# 12V_Horn_Schematic.net
KiCad netlist of a schematic drawn in Altium Designer
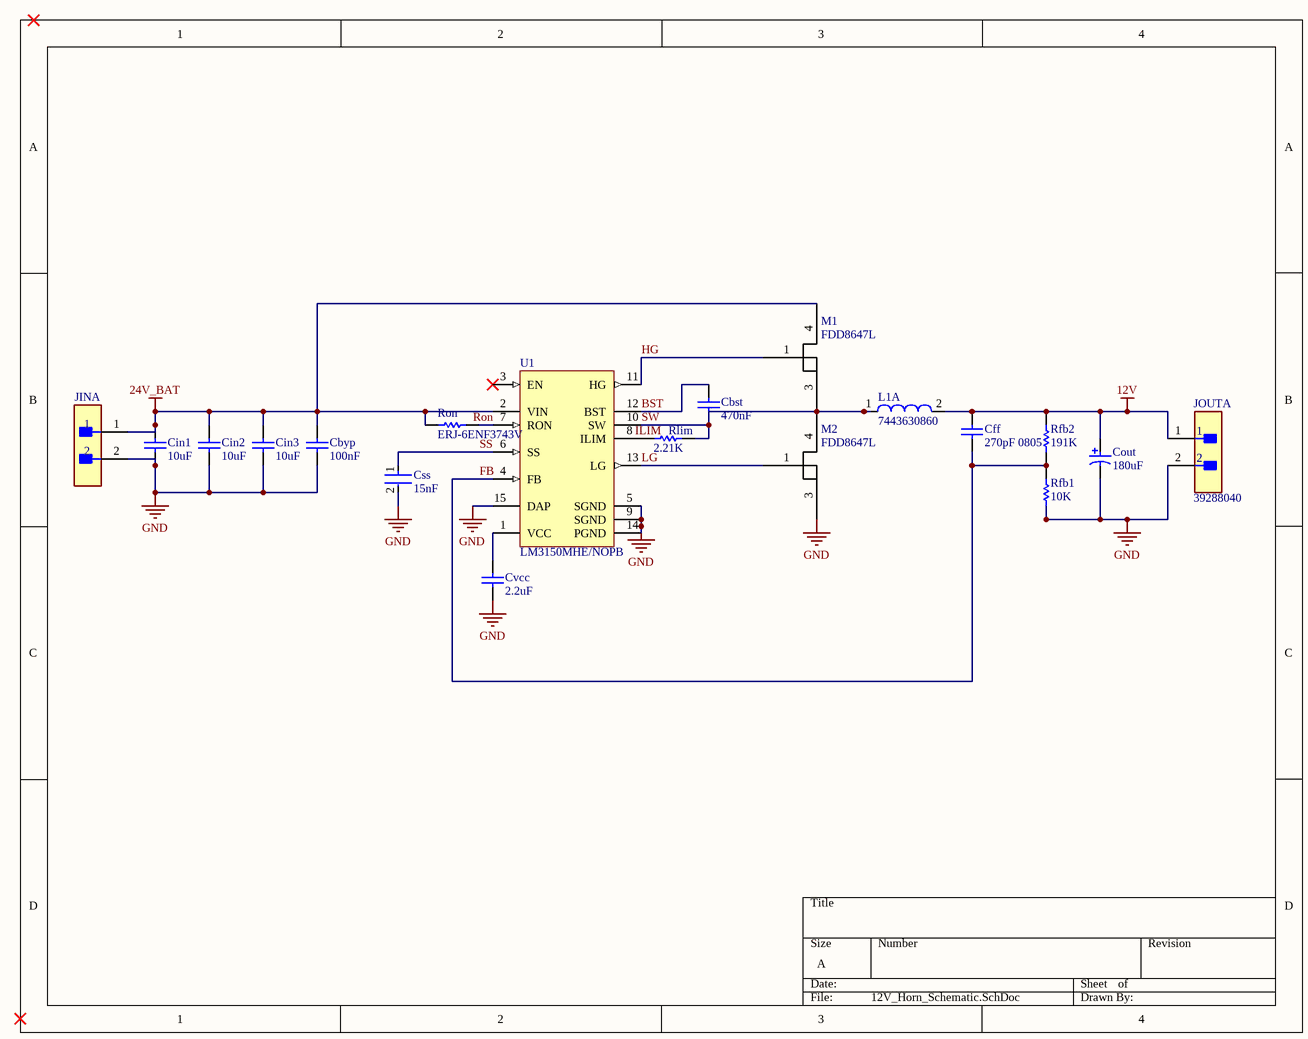
[diagram p0: 12V_Horn_Schematic.SchDoc]

(export (version "E")
  (design (tool "Eeschema 10.0.6"))
  (components
    (comp (ref "Cbst")
      (value "470nF")
      (footprint "CAPC1608X90X35ML10T15")
      (fields (field (name "PART NUMBER") "GRM188R60J474KA01D") (field (name "MANUFACTURER") "Murata"))
      (libsource (lib "Altium Content Vault") (part "CAP"))
    )
    (comp (ref "Cbyp")
      (value "100nF")
      (footprint "CAPC0805(2012)100_M")
      (description "CAP 100nF 50V ±20% 0805 (2012 Metric) Thickness 1mm SMD")
      (fields (field (name "TOLERANCE") "Â±20%"))
      (libsource (lib "Altium Content Vault") (part "CAP"))
    )
    (comp (ref "Cff")
      (value "270pF 0805")
      (footprint "CAPC0805(2012)75_M")
      (description "CAP 270pF 100V ±5% 0805 (2012 Metric) Thickness 0.75mm SMD")
      (fields (field (name "TOLERANCE") "Â±5%"))
      (libsource (lib "Altium Content Vault") (part "CAP"))
    )
    (comp (ref "Cin1")
      (value "10uF")
      (footprint "CAPC3225X270X30LL30")
      (description "Chip Capacitor, 10 uF, +/- 10%, 63 V, -55 to 125 degC, 1210 (3225 Metric), RoHS, Tape and Reel")
      (fields (field (name "VOLTAGE") "63V") (field (name "TOLERANCE") "10%"))
      (libsource (lib "Altium Content Vault") (part "CAP-NP-2"))
    )
    (comp (ref "Cin2")
      (value "10uF")
      (footprint "CAPC3225X270X30LL30")
      (description "Chip Capacitor, 10 uF, +/- 10%, 63 V, -55 to 125 degC, 1210 (3225 Metric), RoHS, Tape and Reel")
      (fields (field (name "VOLTAGE") "63V") (field (name "TOLERANCE") "10%"))
      (libsource (lib "Altium Content Vault") (part "CAP-NP-2"))
    )
    (comp (ref "Cin3")
      (value "10uF")
      (footprint "CAPC3225X270X30LL30")
      (description "Chip Capacitor, 10 uF, +/- 10%, 63 V, -55 to 125 degC, 1210 (3225 Metric), RoHS, Tape and Reel")
      (fields (field (name "VOLTAGE") "63V") (field (name "TOLERANCE") "10%"))
      (libsource (lib "Altium Content Vault") (part "CAP-NP-2"))
    )
    (comp (ref "Cout")
      (value "180uF")
      (footprint "PNSC-SVP-F8_L")
      (fields (field (name "VOLTAGE") "16VDC") (field (name "MANUFACTURER") "Panasonic"))
      (libsource (lib "Altium Content Vault") (part "CAP-P-2"))
    )
    (comp (ref "Css")
      (value "15nF")
      (footprint "FP-CGA4J-IPC_B")
      (description "Cap Ceramic 15nF 50V C0G 5% Pad SMD 0805 +125°C Automotive T/R")
      (fields (field (name "TOLERANCE") "5%"))
      (libsource (lib "Altium Content Vault") (part "b4654b650e69147ec39a6b967a45e02"))
    )
    (comp (ref "Cvcc")
      (value "2.2uF")
      (footprint "CAPC2013X135X50ML10T20")
      (fields (field (name "PART NUMBER") "GRM21BR71A225KA01L") (field (name "MANUFACTURER") "Murata"))
      (libsource (lib "Altium Content Vault") (part "CAP"))
    )
    (comp (ref "JIN")
      (value "39288040")
      (footprint "FP-39288040-MFG")
      (description "CONN HEADER VERT 4POS 4.2MM")
      (fields
        (field (name "MANUFACTURER") "Molex")
        (field (name "OCTOPART") "https://octopart.com/39-28-8040-molex-25241")
      )
      (libsource (lib "") (part "29c4d052ea7803862a8eb5e05759d1e_1"))
    )
    (comp (ref "JOUT")
      (value "39288040")
      (footprint "FP-39288040-MFG")
      (description "CONN HEADER VERT 4POS 4.2MM")
      (fields
        (field (name "MANUFACTURER") "Molex")
        (field (name "OCTOPART") "https://octopart.com/39-28-8040-molex-25241")
      )
      (libsource (lib "Altium Content Vault") (part "29c4d052ea7803862a8eb5e05759d1e"))
    )
    (comp (ref "L1")
      (value "7443630860")
      (footprint "WE-HCF-2013")
      (description "SMD High Current Inductor WE-HCF, L=8.60 µH")
      (libsource (lib "Altium Content Vault") (part "PAS-IND-INDUCTOR-3"))
    )
    (comp (ref "M1") (value "FDD8647L") (footprint "FDD86471L") (libsource (lib "Schlib1") (part "FDD8647L")))
    (comp (ref "M2") (value "FDD8647L") (footprint "FDD86471L") (libsource (lib "Schlib1") (part "FDD8647L")))
    (comp (ref "Rfb1")
      (value "10K")
      (footprint "RESC2013X50X30NL20T20")
      (fields (field (name "MANUFACTURER") "Vishay Dale") (field (name "PART NUMBER") "CRCW080510K0FKEA"))
      (libsource (lib "Altium Content Vault") (part "RES"))
    )
    (comp (ref "Rfb2")
      (value "191K")
      (footprint "RESC2013X70X40ML20T20")
      (fields (field (name "MANUFACTURER") "Panasonic") (field (name "PART NUMBER") "ERJ-6ENF1913V"))
      (libsource (lib "Altium Content Vault") (part "RES"))
    )
    (comp (ref "Rlim")
      (value "2.21K")
      (footprint "RESC2013X50X30NL20T20")
      (fields (field (name "MANUFACTURER") "Vishay Dale") (field (name "PART NUMBER") "CRCW08052K21FKEA"))
      (libsource (lib "Altium Content Vault") (part "RES"))
    )
    (comp (ref "Ron")
      (value "ERJ-6ENF3743V")
      (footprint "RESC2013X70X40LL20T20")
      (fields (field (name "MANUFACTURER") "Panasonic"))
      (libsource (lib "Altium Content Vault") (part "RES"))
    )
    (comp (ref "U1")
      (value "LM3150MHE/NOPB")
      (footprint "PWP0014A_L")
      (description "SIMPLE SWITCHER® CONTROLLER, 42V Synchronous Step-Down, 14-pin TSSOP-EP, Pb-Free")
      (fields (field (name "MANUFACTURER") "Texas Instruments"))
      (libsource (lib "Altium Content Vault") (part "PM-REG-LM3150MH"))
    )
  )
  (nets
    (net (code "1") (name "/BST") (class "Default")
      (node (ref "Cbst") (pin "2") (pinfunction "2_2") (pintype "passive"))
      (node (ref "U1") (pin "12") (pinfunction "BST_12") (pintype "passive"))
    )
    (net (code "2") (name "/FB") (class "Default")
      (node (ref "Cff") (pin "1") (pinfunction "1_1") (pintype "passive"))
      (node (ref "Rfb1") (pin "2") (pinfunction "2_2") (pintype "passive"))
      (node (ref "Rfb2") (pin "1") (pinfunction "1_1") (pintype "passive"))
      (node (ref "U1") (pin "4") (pinfunction "FB_4") (pintype "input"))
    )
    (net (code "3") (name "/HG") (class "Default")
      (node (ref "M1") (pin "1") (pinfunction "G_1") (pintype "passive"))
      (node (ref "U1") (pin "11") (pinfunction "HG_11") (pintype "output"))
    )
    (net (code "5") (name "/LG") (class "Default")
      (node (ref "M2") (pin "1") (pinfunction "G_1") (pintype "passive"))
      (node (ref "U1") (pin "13") (pinfunction "LG_13") (pintype "output"))
    )
    (net (code "7") (name "/SS") (class "Default")
      (node (ref "Css") (pin "1") (pinfunction "1_1") (pintype "passive"))
      (node (ref "U1") (pin "6") (pinfunction "SS_6") (pintype "input"))
    )
    (net (code "8") (name "/SW") (class "Default")
      (node (ref "Cbst") (pin "1") (pinfunction "1_1") (pintype "passive"))
      (node (ref "L1") (pin "1") (pinfunction "1_1") (pintype "passive"))
      (node (ref "M1") (pin "3") (pinfunction "S_3") (pintype "passive"))
      (node (ref "M2") (pin "4") (pinfunction "D_4") (pintype "passive"))
      (node (ref "Rlim") (pin "2") (pinfunction "2_2") (pintype "passive"))
      (node (ref "U1") (pin "10") (pinfunction "SW_10") (pintype "power_in"))
    )
    (net (code "9") (name "12V") (class "Default")
      (node (ref "Cff") (pin "2") (pinfunction "2_2") (pintype "passive"))
      (node (ref "Cout") (pin "1") (pinfunction "1_1") (pintype "passive"))
      (node (ref "JOUT") (pin "1") (pinfunction "1_1") (pintype "passive"))
      (node (ref "L1") (pin "2") (pinfunction "2_2") (pintype "passive"))
      (node (ref "Rfb2") (pin "2") (pinfunction "2_2") (pintype "passive"))
    )
    (net (code "10") (name "24V_BAT") (class "Default")
      (node (ref "Cbyp") (pin "2") (pinfunction "2_2") (pintype "passive"))
      (node (ref "Cin1") (pin "2") (pinfunction "2_2") (pintype "passive"))
      (node (ref "Cin2") (pin "2") (pinfunction "2_2") (pintype "passive"))
      (node (ref "Cin3") (pin "2") (pinfunction "2_2") (pintype "passive"))
      (node (ref "JIN") (pin "1") (pinfunction "1_1") (pintype "passive"))
      (node (ref "M1") (pin "4") (pinfunction "D_4") (pintype "passive"))
      (node (ref "Ron") (pin "1") (pinfunction "1_1") (pintype "passive"))
      (node (ref "U1") (pin "2") (pinfunction "VIN_2") (pintype "power_in"))
    )
    (net (code "11") (name "GND") (class "Default")
      (node (ref "Cbyp") (pin "1") (pinfunction "1_1") (pintype "passive"))
      (node (ref "Cin1") (pin "1") (pinfunction "1_1") (pintype "passive"))
      (node (ref "Cin2") (pin "1") (pinfunction "1_1") (pintype "passive"))
      (node (ref "Cin3") (pin "1") (pinfunction "1_1") (pintype "passive"))
      (node (ref "Cout") (pin "2") (pinfunction "2_2") (pintype "passive"))
      (node (ref "Css") (pin "2") (pinfunction "2_2") (pintype "passive"))
      (node (ref "Cvcc") (pin "1") (pinfunction "1_1") (pintype "passive"))
      (node (ref "JIN") (pin "2") (pinfunction "2_2") (pintype "passive"))
      (node (ref "JOUT") (pin "2") (pinfunction "2_2") (pintype "passive"))
      (node (ref "M2") (pin "3") (pinfunction "S_3") (pintype "passive"))
      (node (ref "Rfb1") (pin "1") (pinfunction "1_1") (pintype "passive"))
      (node (ref "U1") (pin "14") (pinfunction "PGND_14") (pintype "power_in"))
      (node (ref "U1") (pin "15") (pinfunction "DAP_15") (pintype "power_in"))
      (node (ref "U1") (pin "5") (pinfunction "SGND_5") (pintype "power_in"))
      (node (ref "U1") (pin "9") (pinfunction "SGND_9") (pintype "power_in"))
    )
    (net (code "12") (name "Net-(U1-ILIM)") (class "Default")
      (node (ref "Rlim") (pin "1") (pinfunction "1_1") (pintype "passive"))
      (node (ref "U1") (pin "8") (pinfunction "ILIM_8") (pintype "passive"))
    )
    (net (code "13") (name "Net-(U1-RON)") (class "Default")
      (node (ref "Ron") (pin "2") (pinfunction "2_2") (pintype "passive"))
      (node (ref "U1") (pin "7") (pinfunction "RON_7") (pintype "input"))
    )
    (net (code "14") (name "Net-(U1-VCC)") (class "Default")
      (node (ref "Cvcc") (pin "2") (pinfunction "2_2") (pintype "passive"))
      (node (ref "U1") (pin "1") (pinfunction "VCC_1") (pintype "power_in"))
    )
    (net (code "15") (name "unconnected-(U1-EN-Pad3)") (class "Default")
      (node (ref "U1") (pin "3") (pinfunction "EN_3") (pintype "input+no_connect"))
    )
  )
)
